# 0_Overview.net
KiCad netlist of a schematic drawn in Altium Designer
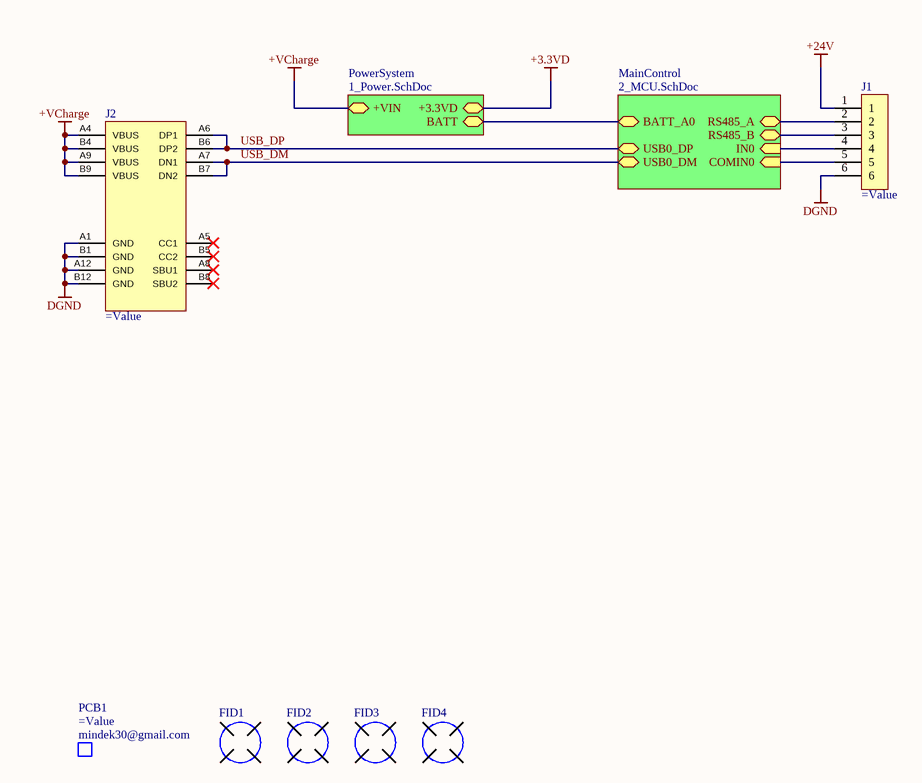
[diagram p0: 0_Overview.SchDoc]

(export (version "E")
  (design (tool "Eeschema 10.0.6"))
  (components
    (comp (ref "FID1")
      (value "FIDUCIAL")
      (footprint "FID")
      (description "Fiducial")
      (fields (field (name "MANUFACTURER") "mindek30@gmail.com") (field (name "PARTNUMBER") "_"))
      (libsource (lib "UUSymbol") (part "FID_FIDUCIAL"))
    )
    (comp (ref "FID2")
      (value "FIDUCIAL")
      (footprint "FID")
      (description "Fiducial")
      (fields (field (name "MANUFACTURER") "mindek30@gmail.com") (field (name "PARTNUMBER") "_"))
      (libsource (lib "UUSymbol") (part "FID_FIDUCIAL"))
    )
    (comp (ref "FID3")
      (value "FIDUCIAL")
      (footprint "FID")
      (description "Fiducial")
      (fields (field (name "MANUFACTURER") "mindek30@gmail.com") (field (name "PARTNUMBER") "_"))
      (libsource (lib "UUSymbol") (part "FID_FIDUCIAL"))
    )
    (comp (ref "FID4")
      (value "FIDUCIAL")
      (footprint "FID")
      (description "Fiducial")
      (fields (field (name "MANUFACTURER") "mindek30@gmail.com") (field (name "PARTNUMBER") "_"))
      (libsource (lib "UUSymbol") (part "FID_FIDUCIAL"))
    )
    (comp (ref "J1")
      (value "~")
      (footprint "CON_6P_Terminal")
      (description "TERM BLOCK HDR 6POS 90DEG 3.5MM")
      (fields (field (name "PARTNUMBER") "1843839") (field (name "MANUFACTURER") "Phoenix Contact"))
      (libsource (lib "UUSymbol") (part "CON_6P_Terminal"))
    )
    (comp (ref "J2")
      (value "~")
      (footprint "2137160001_MOL_2137160001(Primary)")
      (description "CONN RCPT USB2.0 TYPE C 24POS RA")
      (fields (field (name "PARTNUMBER") "2137160001") (field (name "MANUFACTURER") "Molex"))
      (libsource (lib "UUSymbol") (part "CON_USBC"))
    )
    (comp (ref "PCB1")
      (value "~")
      (description "BARE PCB")
      (fields (field (name "MANUFACTURER") "mindek30@gmail.com") (field (name "PARTNUMBER") "_"))
      (libsource (lib "UUSymbol") (part "PCB_Bare"))
    )
  )
  (nets
    (net (code "2") (name "+24V") (class "Default")
      (node (ref "J1") (pin "1") (pinfunction "1_1") (pintype "passive"))
    )
    (net (code "3") (name "+VCharge") (class "Default")
      (node (ref "J2") (pin "A4") (pinfunction "VBUS_A4") (pintype "passive"))
      (node (ref "J2") (pin "A9") (pinfunction "VBUS_A9") (pintype "passive"))
      (node (ref "J2") (pin "B4") (pinfunction "VBUS_B4") (pintype "passive"))
      (node (ref "J2") (pin "B9") (pinfunction "VBUS_B9") (pintype "passive"))
    )
    (net (code "5") (name "/COMIN0") (class "Default")
      (node (ref "J1") (pin "5") (pinfunction "5_5") (pintype "passive"))
    )
    (net (code "6") (name "/IN0") (class "Default")
      (node (ref "J1") (pin "4") (pinfunction "4_4") (pintype "passive"))
    )
    (net (code "7") (name "/RS485_A") (class "Default")
      (node (ref "J1") (pin "2") (pinfunction "2_2") (pintype "passive"))
    )
    (net (code "8") (name "/RS485_B") (class "Default")
      (node (ref "J1") (pin "3") (pinfunction "3_3") (pintype "passive"))
    )
    (net (code "9") (name "/USB_DM") (class "Default")
      (node (ref "J2") (pin "A7") (pinfunction "DN1_A7") (pintype "passive"))
      (node (ref "J2") (pin "B7") (pinfunction "DN2_B7") (pintype "passive"))
    )
    (net (code "10") (name "/USB_DP") (class "Default")
      (node (ref "J2") (pin "A6") (pinfunction "DP1_A6") (pintype "passive"))
      (node (ref "J2") (pin "B6") (pinfunction "DP2_B6") (pintype "passive"))
    )
    (net (code "11") (name "DGND") (class "Default")
      (node (ref "J1") (pin "6") (pinfunction "6_6") (pintype "passive"))
      (node (ref "J2") (pin "A1") (pinfunction "GND_A1") (pintype "passive"))
      (node (ref "J2") (pin "A12") (pinfunction "GND_A12") (pintype "passive"))
      (node (ref "J2") (pin "B1") (pinfunction "GND_B1") (pintype "passive"))
      (node (ref "J2") (pin "B12") (pinfunction "GND_B12") (pintype "passive"))
    )
    (net (code "12") (name "unconnected-(J2-CC1-PadA5)") (class "Default")
      (node (ref "J2") (pin "A5") (pinfunction "CC1_A5") (pintype "passive+no_connect"))
    )
    (net (code "13") (name "unconnected-(J2-CC2-PadB5)") (class "Default")
      (node (ref "J2") (pin "B5") (pinfunction "CC2_B5") (pintype "passive+no_connect"))
    )
    (net (code "14") (name "unconnected-(J2-SBU1-PadA8)") (class "Default")
      (node (ref "J2") (pin "A8") (pinfunction "SBU1_A8") (pintype "passive+no_connect"))
    )
    (net (code "15") (name "unconnected-(J2-SBU2-PadB8)") (class "Default")
      (node (ref "J2") (pin "B8") (pinfunction "SBU2_B8") (pintype "passive+no_connect"))
    )
  )
)
